# Power_Path.net
KiCad netlist of a schematic drawn in Altium Designer
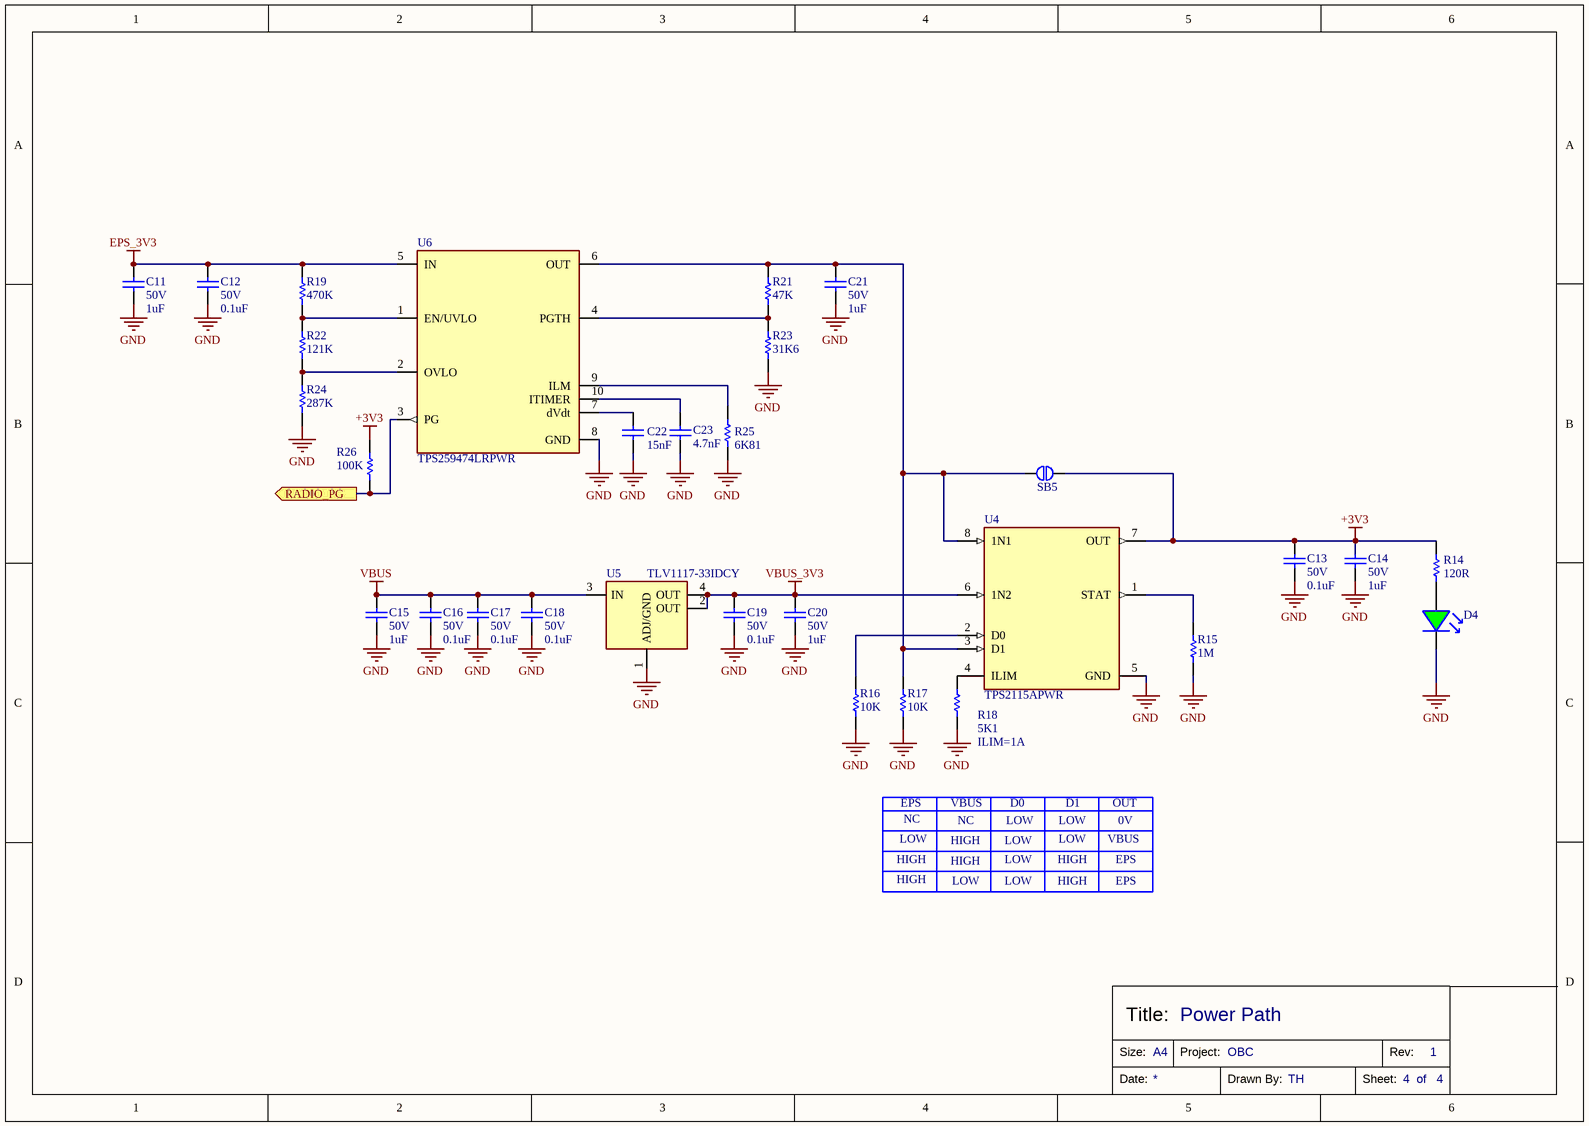
[diagram p0: Power_Path.SchDoc]

(export (version "E")
  (design (tool "Eeschema 10.0.6"))
  (components
    (comp (ref "C11")
      (value "CL21B105KBFNNNE_1")
      (footprint "CAPC0805X060")
      (description "1uF 50V X7R ±10% 0805 Multilayer Ceramic Capacitors MLCC - SMD/SMT ROHS")
      (fields
        (field (name "PART NUMBER") "CL21B105KBFNNNE")
        (field (name "DISTRIBUTOR PART NUMBER") "1276-1029-1-ND")
        (field (name "VOLTAGE RATING") "50V")
        (field (name "CAPACITANCE") "1uF")
      )
      (libsource (lib "Ahristi_Library") (part "CL21B105KBFNNNE_1"))
    )
    (comp (ref "C12")
      (value "CL05B104KB5NNNC")
      (footprint "CAPC0402X020")
      (description "0.1 µF ±10% 50V Ceramic Capacitor X7R 0402 (1005 Metric)")
      (fields
        (field (name "TOLERANCE") "10%")
        (field (name "DISTRIBUTOR PART NUMBER") "1276-CL05B104KB5NNNCCT-ND")
        (field (name "VOLTAGE RATING") "50V")
        (field (name "CAPACITANCE") "0.1uF")
      )
      (libsource (lib "Ahristi_Library") (part "CL05B104KB5NNNC"))
    )
    (comp (ref "C13")
      (value "CL05B104KB5NNNC")
      (footprint "CAPC0402X020")
      (description "0.1 µF ±10% 50V Ceramic Capacitor X7R 0402 (1005 Metric)")
      (fields
        (field (name "TOLERANCE") "10%")
        (field (name "DISTRIBUTOR PART NUMBER") "1276-CL05B104KB5NNNCCT-ND")
        (field (name "VOLTAGE RATING") "50V")
        (field (name "CAPACITANCE") "0.1uF")
      )
      (libsource (lib "Ahristi_Library") (part "CL05B104KB5NNNC"))
    )
    (comp (ref "C14")
      (value "CL21B105KBFNNNE_1")
      (footprint "CAPC0805X060")
      (description "1uF 50V X7R ±10% 0805 Multilayer Ceramic Capacitors MLCC - SMD/SMT ROHS")
      (fields
        (field (name "PART NUMBER") "CL21B105KBFNNNE")
        (field (name "DISTRIBUTOR PART NUMBER") "1276-1029-1-ND")
        (field (name "VOLTAGE RATING") "50V")
        (field (name "CAPACITANCE") "1uF")
      )
      (libsource (lib "Ahristi_Library") (part "CL21B105KBFNNNE_1"))
    )
    (comp (ref "C15")
      (value "CL21B105KBFNNNE_1")
      (footprint "CAPC0805X060")
      (description "1uF 50V X7R ±10% 0805 Multilayer Ceramic Capacitors MLCC - SMD/SMT ROHS")
      (fields
        (field (name "PART NUMBER") "CL21B105KBFNNNE")
        (field (name "DISTRIBUTOR PART NUMBER") "1276-1029-1-ND")
        (field (name "VOLTAGE RATING") "50V")
        (field (name "CAPACITANCE") "1uF")
      )
      (libsource (lib "Ahristi_Library") (part "CL21B105KBFNNNE_1"))
    )
    (comp (ref "C16")
      (value "CL05B104KB5NNNC")
      (footprint "CAPC0402X020")
      (description "0.1 µF ±10% 50V Ceramic Capacitor X7R 0402 (1005 Metric)")
      (fields
        (field (name "TOLERANCE") "10%")
        (field (name "DISTRIBUTOR PART NUMBER") "1276-CL05B104KB5NNNCCT-ND")
        (field (name "VOLTAGE RATING") "50V")
        (field (name "CAPACITANCE") "0.1uF")
      )
      (libsource (lib "Ahristi_Library") (part "CL05B104KB5NNNC"))
    )
    (comp (ref "C17")
      (value "CL05B104KB5NNNC")
      (footprint "CAPC0402X020")
      (description "0.1 µF ±10% 50V Ceramic Capacitor X7R 0402 (1005 Metric)")
      (fields
        (field (name "TOLERANCE") "10%")
        (field (name "DISTRIBUTOR PART NUMBER") "1276-CL05B104KB5NNNCCT-ND")
        (field (name "VOLTAGE RATING") "50V")
        (field (name "CAPACITANCE") "0.1uF")
      )
      (libsource (lib "Ahristi_Library") (part "CL05B104KB5NNNC"))
    )
    (comp (ref "C18")
      (value "CL05B104KB5NNNC")
      (footprint "CAPC0402X020")
      (description "0.1 µF ±10% 50V Ceramic Capacitor X7R 0402 (1005 Metric)")
      (fields
        (field (name "TOLERANCE") "10%")
        (field (name "DISTRIBUTOR PART NUMBER") "1276-CL05B104KB5NNNCCT-ND")
        (field (name "VOLTAGE RATING") "50V")
        (field (name "CAPACITANCE") "0.1uF")
      )
      (libsource (lib "Ahristi_Library") (part "CL05B104KB5NNNC"))
    )
    (comp (ref "C19")
      (value "CL05B104KB5NNNC")
      (footprint "CAPC0402X020")
      (description "0.1 µF ±10% 50V Ceramic Capacitor X7R 0402 (1005 Metric)")
      (fields
        (field (name "TOLERANCE") "10%")
        (field (name "DISTRIBUTOR PART NUMBER") "1276-CL05B104KB5NNNCCT-ND")
        (field (name "VOLTAGE RATING") "50V")
        (field (name "CAPACITANCE") "0.1uF")
      )
      (libsource (lib "Ahristi_Library") (part "CL05B104KB5NNNC"))
    )
    (comp (ref "C20")
      (value "CL21B105KBFNNNE_1")
      (footprint "CAPC0805X060")
      (description "1uF 50V X7R ±10% 0805 Multilayer Ceramic Capacitors MLCC - SMD/SMT ROHS")
      (fields
        (field (name "PART NUMBER") "CL21B105KBFNNNE")
        (field (name "DISTRIBUTOR PART NUMBER") "1276-1029-1-ND")
        (field (name "VOLTAGE RATING") "50V")
        (field (name "CAPACITANCE") "1uF")
      )
      (libsource (lib "Ahristi_Library") (part "CL21B105KBFNNNE_1"))
    )
    (comp (ref "C21")
      (value "CL21B105KBFNNNE_1")
      (footprint "CAPC0805X060")
      (description "1uF 50V X7R ±10% 0805 Multilayer Ceramic Capacitors MLCC - SMD/SMT ROHS")
      (fields
        (field (name "PART NUMBER") "CL21B105KBFNNNE")
        (field (name "DISTRIBUTOR PART NUMBER") "1276-1029-1-ND")
        (field (name "VOLTAGE RATING") "50V")
        (field (name "CAPACITANCE") "1uF")
      )
      (libsource (lib "Ahristi_Library") (part "CL21B105KBFNNNE_1"))
    )
    (comp (ref "C22")
      (value "C0603C153F3GACTU")
      (footprint "CAPC0603X040")
      (description "0.015 µF ±1% 25V Ceramic Capacitor C0G, NP0 0603 (1608 Metric)")
      (fields
        (field (name "TOLERANCE") "1%")
        (field (name "DISTRIBUTOR PART NUMBER") "399-C0603C153F3GACTUCT-ND")
        (field (name "CAPACITANCE") "15nF")
      )
      (libsource (lib "Ahristi_Library") (part "C0603C153F3GACTU"))
    )
    (comp (ref "C23")
      (value "CL21B105KAFNNNE")
      (footprint "CAPC0805X060")
      (description "4.7nF ±10% 50V Ceramic Capacitor X7R 0805 (2012 Metric)")
      (fields
        (field (name "PART NUMBER") "CL21B472KBANNNC")
        (field (name "DISTRIBUTOR PART NUMBER") "1276-1155-1-ND")
        (field (name "CAPACITANCE") "4.7nF")
      )
      (libsource (lib "Ahristi_Library") (part "CL21B472KBANNNC"))
    )
    (comp (ref "D4")
      (value "LTST-C171KGKT")
      (footprint "LEDG_0805")
      (description "LED Green 0805 00mW 120° 2.6V~3.1V 430mcd 513nm~528nm 525nm 5mA")
      (fields (field (name "DISTRIBUTOR PART NUMBER") "160-1426-1-ND"))
      (libsource (lib "Ahristi_Library") (part "KT-0805G"))
    )
    (comp (ref "R14")
      (value "RMCF0805FT120R")
      (footprint "RESC0805")
      (description "120 Ohms ±1% 0.125W, 1/8W Chip Resistor 0805 (2012 Metric) Automotive AEC-Q200 Thick Film")
      (fields
        (field (name "TOLERANCE") "1%")
        (field (name "DISTRIBUTOR PART NUMBER") "738-RMCF0805FT120RCT-ND")
        (field (name "RESISTANCE") "120R")
      )
      (libsource (lib "Ahristi_Library") (part "RMCF0805FT120R"))
    )
    (comp (ref "R15")
      (value "RMCF0603FT1M00")
      (footprint "RESC0603")
      (description "1 MOhms ±1% 0.1W, 1/10W Chip Resistor 0603 (1608 Metric) Automotive AEC-Q200 Thick Film")
      (fields
        (field (name "TOLERANCE") "1%")
        (field (name "DISTRIBUTOR PART NUMBER") "RMCF0603FT1M00CT-ND")
        (field (name "RESISTANCE") "1M")
      )
      (libsource (lib "Ahristi_Library") (part "RMCF0603FT1M00"))
    )
    (comp (ref "R16")
      (value "RMCF0805FT10K0")
      (footprint "RESC0805")
      (description "10 kOhms ±1% 0.125W, 1/8W Chip Resistor 0805 (2012 Metric) Automotive AEC-Q200 Thick Film")
      (fields
        (field (name "TOLERANCE") "1%")
        (field (name "DISTRIBUTOR PART NUMBER") "RMCF0805FT10K0CT-ND")
        (field (name "RESISTANCE") "10K")
      )
      (libsource (lib "Ahristi_Library") (part "RMCF0805FT10K0"))
    )
    (comp (ref "R17")
      (value "RMCF0805FT10K0")
      (footprint "RESC0805")
      (description "10 kOhms ±1% 0.125W, 1/8W Chip Resistor 0805 (2012 Metric) Automotive AEC-Q200 Thick Film")
      (fields
        (field (name "TOLERANCE") "1%")
        (field (name "DISTRIBUTOR PART NUMBER") "RMCF0805FT10K0CT-ND")
        (field (name "RESISTANCE") "10K")
      )
      (libsource (lib "Ahristi_Library") (part "RMCF0805FT10K0"))
    )
    (comp (ref "R18")
      (value "RMCF0603FT5K10")
      (footprint "RESC0603")
      (description "5.1 kOhms ±1% 0.1W, 1/10W Chip Resistor 0603 (1608 Metric) Automotive AEC-Q200 Thick Film")
      (fields
        (field (name "TOLERANCE") "1%")
        (field (name "DISTRIBUTOR PART NUMBER") "RMCF0603FT5K10CT-ND")
        (field (name "RESISTANCE") "5K1")
      )
      (libsource (lib "Ahristi_Library") (part "RMCF0603FT5K10"))
    )
    (comp (ref "R19")
      (value "RMCF0603FT470K")
      (footprint "RESC0603")
      (description "470 kOhms ±1% 0.1W, 1/10W Chip Resistor 0603 (1608 Metric) Automotive AEC-Q200 Thick Film")
      (fields
        (field (name "TOLERANCE") "1%")
        (field (name "DISTRIBUTOR PART NUMBER") "RMCF0603FT470KCT-ND")
        (field (name "RESISTANCE") "470K")
      )
      (libsource (lib "Ahristi_Library") (part "RMCF0603FT470K"))
    )
    (comp (ref "R21")
      (value "RMCF0603FT47K0")
      (footprint "RESC0603")
      (description "47 kOhms ±1% 0.1W, 1/10W Chip Resistor 0603 (1608 Metric) Automotive AEC-Q200 Thick Film")
      (fields
        (field (name "TOLERANCE") "1%")
        (field (name "DISTRIBUTOR PART NUMBER") "RMCF0603FT47K0CT-ND")
        (field (name "RESISTANCE") "47K")
      )
      (libsource (lib "Ahristi_Library") (part "RMCF0603FT47K0"))
    )
    (comp (ref "R22")
      (value "RMCF0603FT121K")
      (footprint "RESC0603")
      (description "121 kOhms ±1% 0.1W, 1/10W Chip Resistor 0603 (1608 Metric) Automotive AEC-Q200 Thick Film")
      (fields
        (field (name "TOLERANCE") "1%")
        (field (name "DISTRIBUTOR PART NUMBER") "RMCF0603FT121KCT-ND")
        (field (name "RESISTANCE") "121K")
      )
      (libsource (lib "Ahristi_Library") (part "RMCF0603FT121K"))
    )
    (comp (ref "R23")
      (value "RMCF0603FT31K6")
      (footprint "RESC0603")
      (description "31.6 kOhms ±1% 0.1W, 1/10W Chip Resistor 0603 (1608 Metric) Automotive AEC-Q200 Thick Film")
      (fields
        (field (name "TOLERANCE") "1%")
        (field (name "DISTRIBUTOR PART NUMBER") "RMCF0603FT31K6CT-ND")
        (field (name "RESISTANCE") "31K6")
      )
      (libsource (lib "Ahristi_Library") (part "RMCF0603FT31K6"))
    )
    (comp (ref "R24")
      (value "RMCF0603FT287K")
      (footprint "RESC0603")
      (description "287 kOhms ±1% 0.1W, 1/10W Chip Resistor 0603 (1608 Metric) Automotive AEC-Q200 Thick Film")
      (fields
        (field (name "TOLERANCE") "1%")
        (field (name "DISTRIBUTOR PART NUMBER") "RMCF0603FT287KCT-ND")
        (field (name "RESISTANCE") "287K")
      )
      (libsource (lib "Ahristi_Library") (part "RMCF0603FT287K"))
    )
    (comp (ref "R25")
      (value "RMCF0603FT6K81")
      (footprint "RESC0603")
      (description "6.81 kOhms ±1% 0.1W, 1/10W Chip Resistor 0603 (1608 Metric) Automotive AEC-Q200 Thick Film")
      (fields
        (field (name "TOLERANCE") "1%")
        (field (name "DISTRIBUTOR PART NUMBER") "RMCF0603FT6K81CT-ND")
        (field (name "RESISTANCE") "6K81")
      )
      (libsource (lib "Ahristi_Library") (part "RMCF0603FT6K81"))
    )
    (comp (ref "R26")
      (value "RMCF0805FG100K")
      (footprint "RESC0805")
      (description "100 kOhms ±1% 0.125W, 1/8W Chip Resistor 0805 (2012 Metric) Automotive AEC-Q200 Thick Film")
      (fields
        (field (name "TOLERANCE") "1%")
        (field (name "DISTRIBUTOR PART NUMBER") "RMCF0805FG100KCT-ND")
        (field (name "RESISTANCE") "100K")
      )
      (libsource (lib "Ahristi_Library") (part "RMCF0805FG100K"))
    )
    (comp (ref "SB5")
      (value "Solder Bridge Jumper")
      (footprint "Solder Bridge")
      (libsource (lib "Ahristi_Library") (part "Solder Bridge Jumper"))
    )
    (comp (ref "U4")
      (value "TPS2115APWR")
      (footprint "8-TSSOP")
      (fields
        (field (name "DISTRIBUTOR PART NUMBER") "296-16940-1-ND")
        (field (name "MANUFACTURER PART NUMBER") "TPS2115APWR")
      )
      (libsource (lib "Ahristi_Library") (part "TPS2115APWR"))
    )
    (comp (ref "U5")
      (value "TLV1117-33IDCY")
      (footprint "TLV1117-33IDCY")
      (description "3.3V 800-mA, 15-V, linear voltage regulator 4-SOT-223 -40 to 125")
      (fields (field (name "DISTRIBUTOR PART NUMBER") "296-26777-5-ND"))
      (libsource (lib "Ahristi_Library") (part "TLV1117-33IDCY"))
    )
    (comp (ref "U6")
      (value "TPS259474LRPWR")
      (footprint "VFQFN-10")
      (description "eFuse 5.5A, 2.7V~23V, 28mOhm, Reverse Current Blocking with Input Reverse Polarity Protection")
      (fields (field (name "DISTRIBUTOR PART NUMBER") "296-TPS259474LRPWRCT-ND"))
      (libsource (lib "Ahristi_Library") (part "TPS259474LRPWR"))
    )
  )
  (nets
    (net (code "1") (name "+3V3") (class "Default")
      (node (ref "C13") (pin "2") (pinfunction "2_2") (pintype "passive"))
      (node (ref "C14") (pin "2") (pinfunction "2_2") (pintype "passive"))
      (node (ref "R14") (pin "2") (pinfunction "2_2") (pintype "passive"))
      (node (ref "R26") (pin "2") (pinfunction "2_2") (pintype "passive"))
      (node (ref "SB5") (pin "2") (pinfunction "2_2") (pintype "passive"))
      (node (ref "U4") (pin "7") (pinfunction "OUT_7") (pintype "output"))
    )
    (net (code "2") (name "/RADIO_PG") (class "Default")
      (node (ref "R26") (pin "1") (pinfunction "1_1") (pintype "passive"))
      (node (ref "U6") (pin "3") (pinfunction "PG_3") (pintype "output"))
    )
    (net (code "3") (name "EPS_3V3") (class "Default")
      (node (ref "C11") (pin "2") (pinfunction "2_2") (pintype "passive"))
      (node (ref "C12") (pin "2") (pinfunction "2_2") (pintype "passive"))
      (node (ref "R19") (pin "2") (pinfunction "2_2") (pintype "passive"))
      (node (ref "U6") (pin "5") (pinfunction "IN_5") (pintype "passive"))
    )
    (net (code "4") (name "GND") (class "Default")
      (node (ref "C11") (pin "1") (pinfunction "1_1") (pintype "passive"))
      (node (ref "C12") (pin "1") (pinfunction "1_1") (pintype "passive"))
      (node (ref "C13") (pin "1") (pinfunction "1_1") (pintype "passive"))
      (node (ref "C14") (pin "1") (pinfunction "1_1") (pintype "passive"))
      (node (ref "C15") (pin "1") (pinfunction "1_1") (pintype "passive"))
      (node (ref "C16") (pin "1") (pinfunction "1_1") (pintype "passive"))
      (node (ref "C17") (pin "1") (pinfunction "1_1") (pintype "passive"))
      (node (ref "C18") (pin "1") (pinfunction "1_1") (pintype "passive"))
      (node (ref "C19") (pin "1") (pinfunction "1_1") (pintype "passive"))
      (node (ref "C20") (pin "1") (pinfunction "1_1") (pintype "passive"))
      (node (ref "C21") (pin "1") (pinfunction "1_1") (pintype "passive"))
      (node (ref "C22") (pin "1") (pinfunction "1_1") (pintype "passive"))
      (node (ref "C23") (pin "1") (pinfunction "1_1") (pintype "passive"))
      (node (ref "D4") (pin "K") (pinfunction "K_K") (pintype "passive"))
      (node (ref "R15") (pin "1") (pinfunction "1_1") (pintype "passive"))
      (node (ref "R16") (pin "1") (pinfunction "1_1") (pintype "passive"))
      (node (ref "R17") (pin "1") (pinfunction "1_1") (pintype "passive"))
      (node (ref "R18") (pin "1") (pinfunction "1_1") (pintype "passive"))
      (node (ref "R23") (pin "1") (pinfunction "1_1") (pintype "passive"))
      (node (ref "R24") (pin "1") (pinfunction "1_1") (pintype "passive"))
      (node (ref "R25") (pin "1") (pinfunction "1_1") (pintype "passive"))
      (node (ref "U4") (pin "5") (pinfunction "GND_5") (pintype "passive"))
      (node (ref "U5") (pin "1") (pinfunction "ADJ/GND_1") (pintype "passive"))
      (node (ref "U6") (pin "8") (pinfunction "GND_8") (pintype "passive"))
    )
    (net (code "5") (name "Net-(D4-PadA)") (class "Default")
      (node (ref "D4") (pin "A") (pinfunction "A_A") (pintype "passive"))
      (node (ref "R14") (pin "1") (pinfunction "1_1") (pintype "passive"))
    )
    (net (code "6") (name "Net-(U4-1N1)") (class "Default")
      (node (ref "C21") (pin "2") (pinfunction "2_2") (pintype "passive"))
      (node (ref "R17") (pin "2") (pinfunction "2_2") (pintype "passive"))
      (node (ref "R21") (pin "2") (pinfunction "2_2") (pintype "passive"))
      (node (ref "SB5") (pin "1") (pinfunction "1_1") (pintype "passive"))
      (node (ref "U4") (pin "3") (pinfunction "D1_3") (pintype "input"))
      (node (ref "U4") (pin "8") (pinfunction "1N1_8") (pintype "input"))
      (node (ref "U6") (pin "6") (pinfunction "OUT_6") (pintype "passive"))
    )
    (net (code "7") (name "Net-(U4-D0)") (class "Default")
      (node (ref "R16") (pin "2") (pinfunction "2_2") (pintype "passive"))
      (node (ref "U4") (pin "2") (pinfunction "D0_2") (pintype "input"))
    )
    (net (code "8") (name "Net-(U4-ILIM)") (class "Default")
      (node (ref "R18") (pin "2") (pinfunction "2_2") (pintype "passive"))
      (node (ref "U4") (pin "4") (pinfunction "ILIM_4") (pintype "passive"))
    )
    (net (code "9") (name "Net-(U4-STAT)") (class "Default")
      (node (ref "R15") (pin "2") (pinfunction "2_2") (pintype "passive"))
      (node (ref "U4") (pin "1") (pinfunction "STAT_1") (pintype "output"))
    )
    (net (code "10") (name "Net-(U6-EN{slash}UVLO)") (class "Default")
      (node (ref "R19") (pin "1") (pinfunction "1_1") (pintype "passive"))
      (node (ref "R22") (pin "2") (pinfunction "2_2") (pintype "passive"))
      (node (ref "U6") (pin "1") (pinfunction "EN/UVLO_1") (pintype "passive"))
    )
    (net (code "11") (name "Net-(U6-ILM)") (class "Default")
      (node (ref "R25") (pin "2") (pinfunction "2_2") (pintype "passive"))
      (node (ref "U6") (pin "9") (pinfunction "ILM_9") (pintype "passive"))
    )
    (net (code "12") (name "Net-(U6-ITIMER)") (class "Default")
      (node (ref "C23") (pin "2") (pinfunction "2_2") (pintype "passive"))
      (node (ref "U6") (pin "10") (pinfunction "ITIMER_10") (pintype "passive"))
    )
    (net (code "13") (name "Net-(U6-OVLO)") (class "Default")
      (node (ref "R22") (pin "1") (pinfunction "1_1") (pintype "passive"))
      (node (ref "R24") (pin "2") (pinfunction "2_2") (pintype "passive"))
      (node (ref "U6") (pin "2") (pinfunction "OVLO_2") (pintype "passive"))
    )
    (net (code "14") (name "Net-(U6-PGTH)") (class "Default")
      (node (ref "R21") (pin "1") (pinfunction "1_1") (pintype "passive"))
      (node (ref "R23") (pin "2") (pinfunction "2_2") (pintype "passive"))
      (node (ref "U6") (pin "4") (pinfunction "PGTH_4") (pintype "passive"))
    )
    (net (code "15") (name "Net-(U6-dVdt)") (class "Default")
      (node (ref "C22") (pin "2") (pinfunction "2_2") (pintype "passive"))
      (node (ref "U6") (pin "7") (pinfunction "dVdt_7") (pintype "passive"))
    )
    (net (code "16") (name "VBUS") (class "Default")
      (node (ref "C15") (pin "2") (pinfunction "2_2") (pintype "passive"))
      (node (ref "C16") (pin "2") (pinfunction "2_2") (pintype "passive"))
      (node (ref "C17") (pin "2") (pinfunction "2_2") (pintype "passive"))
      (node (ref "C18") (pin "2") (pinfunction "2_2") (pintype "passive"))
      (node (ref "U5") (pin "3") (pinfunction "IN_3") (pintype "passive"))
    )
    (net (code "17") (name "VBUS_3V3") (class "Default")
      (node (ref "C19") (pin "2") (pinfunction "2_2") (pintype "passive"))
      (node (ref "C20") (pin "2") (pinfunction "2_2") (pintype "passive"))
      (node (ref "U4") (pin "6") (pinfunction "1N2_6") (pintype "input"))
      (node (ref "U5") (pin "2") (pinfunction "OUT_2") (pintype "passive"))
      (node (ref "U5") (pin "4") (pinfunction "OUT_4") (pintype "passive"))
    )
  )
)
